# megy_dole_v1.net
KiCad netlist of a schematic drawn in EAGLE
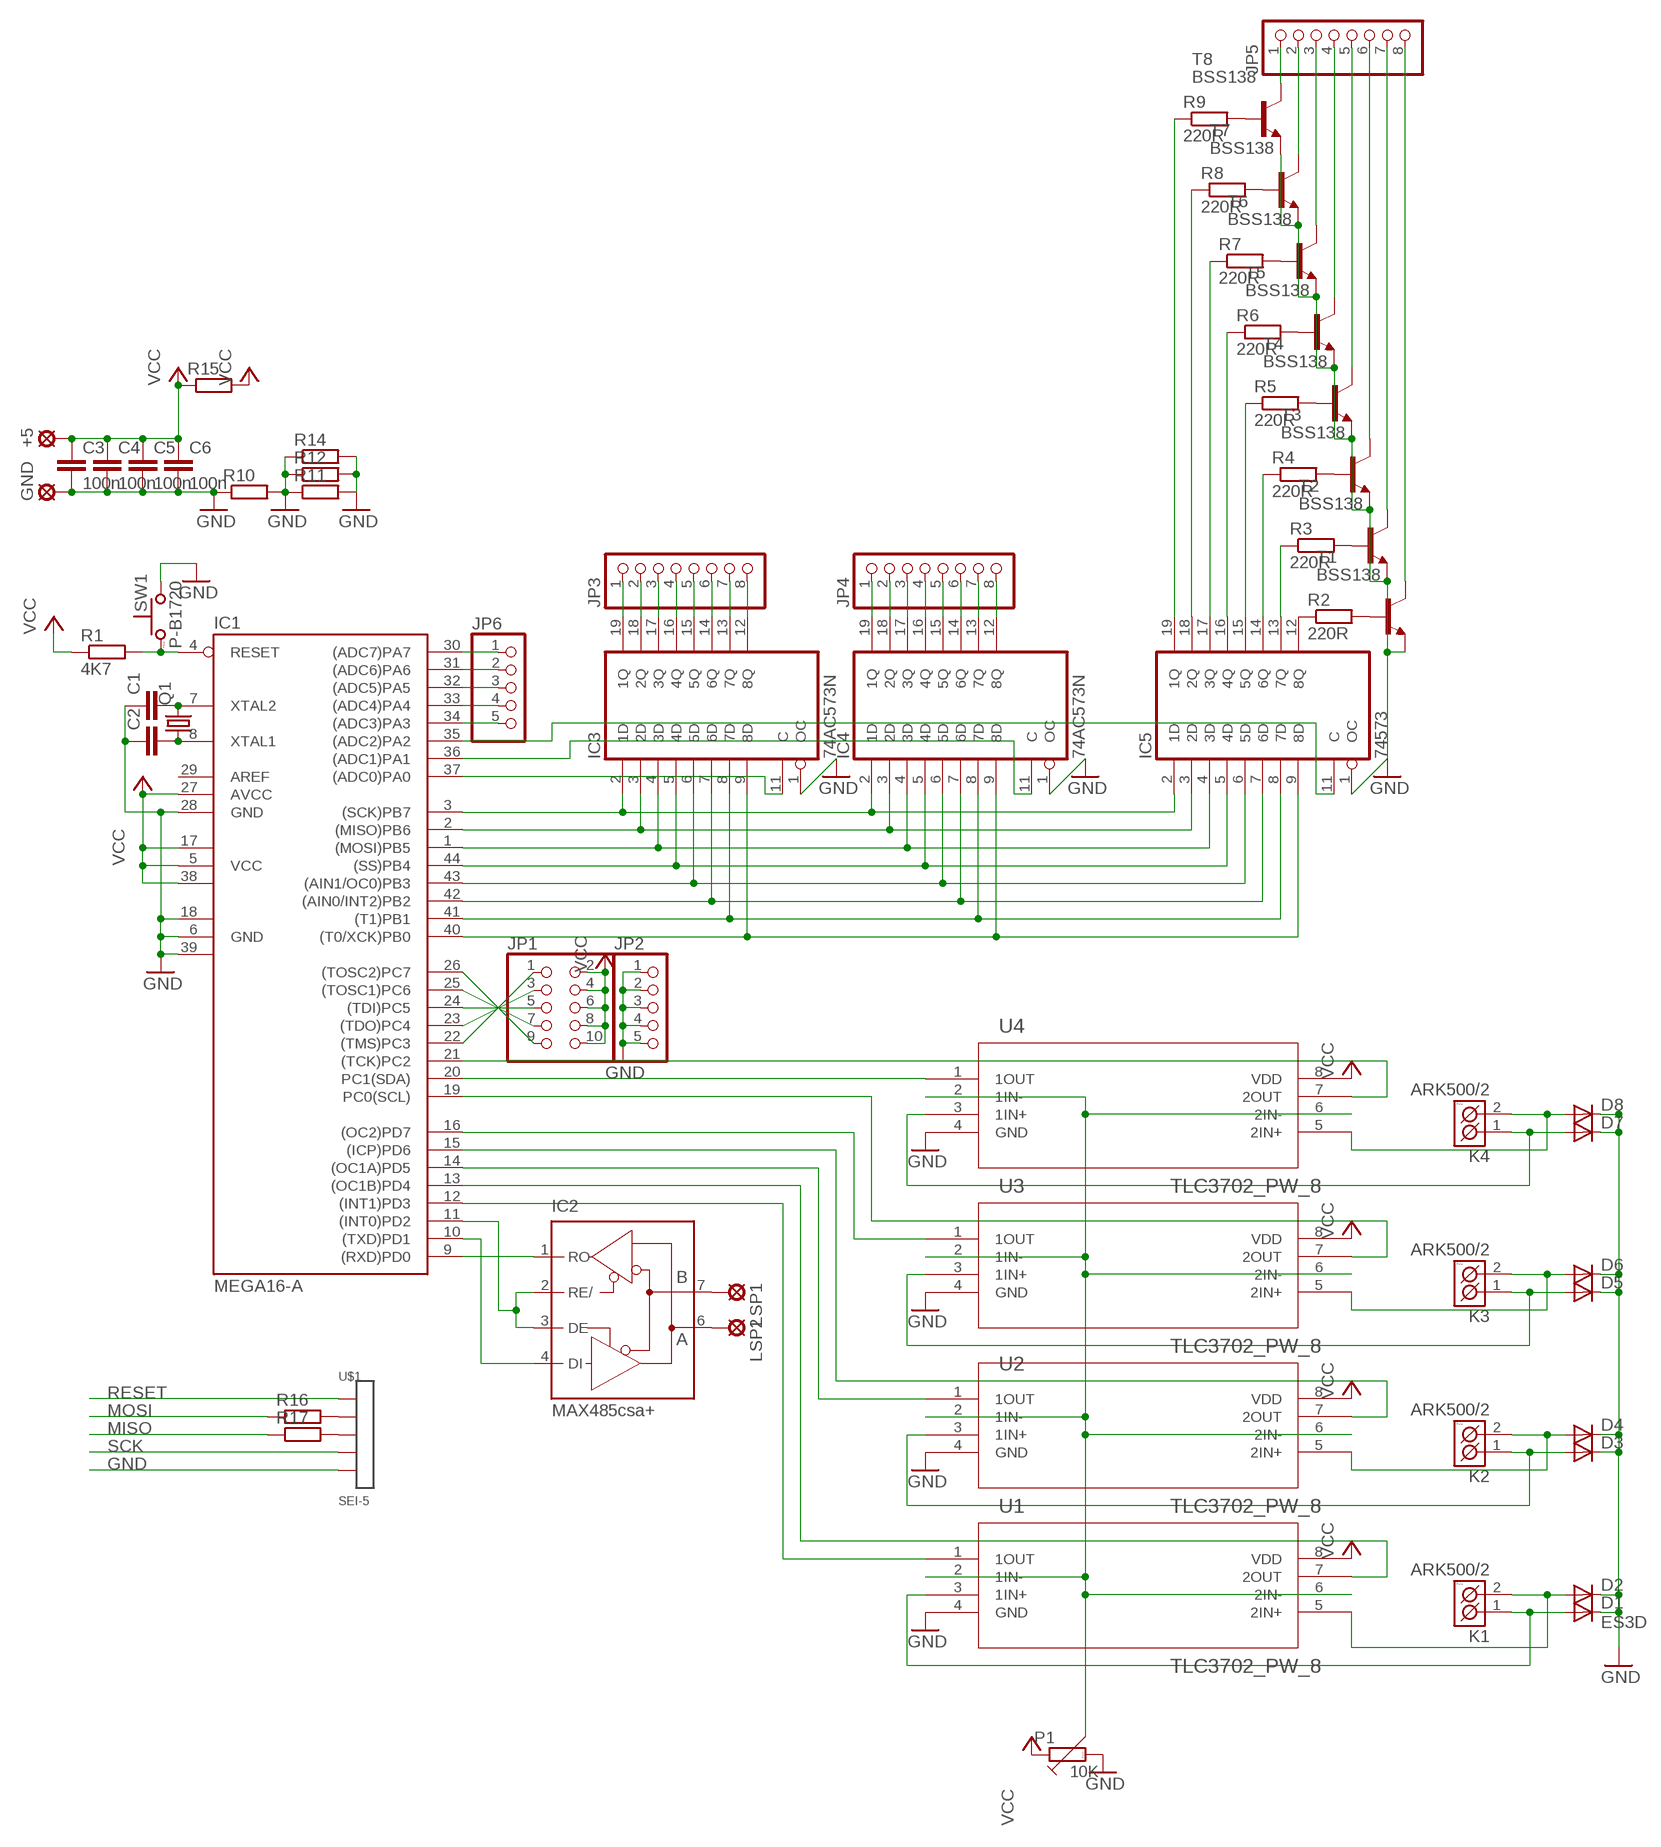
[diagram p0: schematic, sheet 1]

(export (version "E")
  (design (tool "Eeschema 10.0.6"))
  (components
    (comp (ref "+5")
      (value "LSP10")
      (footprint "eagle-import:LSP10")
      (libsource (lib "eagle-import") (part "LSP10"))
    )
    (comp (ref "C1")
      (value "C-EUC0603")
      (footprint "eagle-import:C0603")
      (libsource (lib "eagle-import") (part "C-EUC0603"))
    )
    (comp (ref "C2")
      (value "C-EUC0603")
      (footprint "eagle-import:C0603")
      (libsource (lib "eagle-import") (part "C-EUC0603"))
    )
    (comp (ref "C3")
      (value "100n")
      (footprint "eagle-import:C0504")
      (libsource (lib "eagle-import") (part "C-EUC0504"))
    )
    (comp (ref "C4")
      (value "100n")
      (footprint "eagle-import:C0504")
      (libsource (lib "eagle-import") (part "C-EUC0504"))
    )
    (comp (ref "C5")
      (value "100n")
      (footprint "eagle-import:C0504")
      (libsource (lib "eagle-import") (part "C-EUC0504"))
    )
    (comp (ref "C6")
      (value "100n")
      (footprint "eagle-import:C0504")
      (libsource (lib "eagle-import") (part "C-EUC0504"))
    )
    (comp (ref "D1")
      (value "ES3D")
      (footprint "eagle-import:SMC")
      (libsource (lib "eagle-import") (part "DIODE-SMC"))
    )
    (comp (ref "D2")
      (value "DIODE-SMC")
      (footprint "eagle-import:SMC")
      (libsource (lib "eagle-import") (part "DIODE-SMC"))
    )
    (comp (ref "D3")
      (value "DIODE-SMC")
      (footprint "eagle-import:SMC")
      (libsource (lib "eagle-import") (part "DIODE-SMC"))
    )
    (comp (ref "D4")
      (value "DIODE-SMC")
      (footprint "eagle-import:SMC")
      (libsource (lib "eagle-import") (part "DIODE-SMC"))
    )
    (comp (ref "D5")
      (value "DIODE-SMC")
      (footprint "eagle-import:SMC")
      (libsource (lib "eagle-import") (part "DIODE-SMC"))
    )
    (comp (ref "D6")
      (value "DIODE-SMC")
      (footprint "eagle-import:SMC")
      (libsource (lib "eagle-import") (part "DIODE-SMC"))
    )
    (comp (ref "D7")
      (value "DIODE-SMC")
      (footprint "eagle-import:SMC")
      (libsource (lib "eagle-import") (part "DIODE-SMC"))
    )
    (comp (ref "D8")
      (value "DIODE-SMC")
      (footprint "eagle-import:SMC")
      (libsource (lib "eagle-import") (part "DIODE-SMC"))
    )
    (comp (ref "GND")
      (value "LSP10")
      (footprint "eagle-import:LSP10")
      (libsource (lib "eagle-import") (part "LSP10"))
    )
    (comp (ref "IC1")
      (value "MEGA16-A")
      (footprint "eagle-import:TQFP44")
      (fields (field (name "MPN") "ATMEGA16-16AU"))
      (libsource (lib "eagle-import") (part "MEGA16-A"))
    )
    (comp (ref "IC2")
      (value "MAX485csa+")
      (footprint "eagle-import:SO08")
      (fields
        (field (name "MF") "MAXIM")
        (field (name "MPN") "MAX481CSA")
        (field (name "MF_1") "MAXIM")
        (field (name "MPN_1") "MAX481CSA")
        (field (name "OC_NEWARK") "90C3817")
      )
      (libsource (lib "eagle-import") (part "MAX481CSA"))
    )
    (comp (ref "IC3")
      (value "74AC573N")
      (footprint "eagle-import:DIL20")
      (libsource (lib "eagle-import") (part "74573NAC"))
    )
    (comp (ref "IC4")
      (value "74AC573N")
      (footprint "eagle-import:DIL20")
      (libsource (lib "eagle-import") (part "74573NAC"))
    )
    (comp (ref "IC5")
      (value "74573")
      (footprint "eagle-import:PW20")
      (libsource (lib "eagle-import") (part "74573"))
    )
    (comp (ref "JP1")
      (value "PINHD-2X5")
      (footprint "eagle-import:2X05")
      (libsource (lib "eagle-import") (part "PINHD-2X5"))
    )
    (comp (ref "JP2")
      (value "PINHD-1X5")
      (footprint "eagle-import:1X05")
      (libsource (lib "eagle-import") (part "PINHD-1X5"))
    )
    (comp (ref "JP3")
      (value "PINHD-1X8")
      (footprint "eagle-import:1X08")
      (libsource (lib "eagle-import") (part "PINHD-1X8"))
    )
    (comp (ref "JP4")
      (value "PINHD-1X8")
      (footprint "eagle-import:1X08")
      (libsource (lib "eagle-import") (part "PINHD-1X8"))
    )
    (comp (ref "JP5")
      (value "PINHD-1X8")
      (footprint "eagle-import:1X08")
      (libsource (lib "eagle-import") (part "PINHD-1X8"))
    )
    (comp (ref "JP6")
      (value "PINHD-1X5")
      (footprint "eagle-import:1X05")
      (libsource (lib "eagle-import") (part "PINHD-1X5"))
    )
    (comp (ref "K1")
      (value "ARK500/2")
      (footprint "eagle-import:ARK500_2")
      (libsource (lib "eagle-import") (part "ARK500/2"))
    )
    (comp (ref "K2")
      (value "ARK500/2")
      (footprint "eagle-import:ARK500_2")
      (libsource (lib "eagle-import") (part "ARK500/2"))
    )
    (comp (ref "K3")
      (value "ARK500/2")
      (footprint "eagle-import:ARK500_2")
      (libsource (lib "eagle-import") (part "ARK500/2"))
    )
    (comp (ref "K4")
      (value "ARK500/2")
      (footprint "eagle-import:ARK500_2")
      (libsource (lib "eagle-import") (part "ARK500/2"))
    )
    (comp (ref "LSP1")
      (value "LSP10")
      (footprint "eagle-import:LSP10")
      (libsource (lib "eagle-import") (part "LSP10"))
    )
    (comp (ref "LSP2")
      (value "LSP10")
      (footprint "eagle-import:LSP10")
      (libsource (lib "eagle-import") (part "LSP10"))
    )
    (comp (ref "P1")
      (value "10K")
      (footprint "eagle-import:PM19")
      (libsource (lib "eagle-import") (part "TRIMRPM19"))
    )
    (comp (ref "Q1")
      (value "CRYSTALHC49UP")
      (footprint "eagle-import:HC49UP")
      (libsource (lib "eagle-import") (part "CRYSTALHC49UP"))
    )
    (comp (ref "R1")
      (value "4K7")
      (footprint "eagle-import:R0402")
      (libsource (lib "eagle-import") (part "R-EU_R0402"))
    )
    (comp (ref "R2")
      (value "220R")
      (footprint "eagle-import:R0402")
      (libsource (lib "eagle-import") (part "R-EU_R0402"))
    )
    (comp (ref "R3")
      (value "220R")
      (footprint "eagle-import:R0402")
      (libsource (lib "eagle-import") (part "R-EU_R0402"))
    )
    (comp (ref "R4")
      (value "220R")
      (footprint "eagle-import:R0402")
      (libsource (lib "eagle-import") (part "R-EU_R0402"))
    )
    (comp (ref "R5")
      (value "220R")
      (footprint "eagle-import:R0402")
      (libsource (lib "eagle-import") (part "R-EU_R0402"))
    )
    (comp (ref "R6")
      (value "220R")
      (footprint "eagle-import:R0402")
      (libsource (lib "eagle-import") (part "R-EU_R0402"))
    )
    (comp (ref "R7")
      (value "220R")
      (footprint "eagle-import:R0402")
      (libsource (lib "eagle-import") (part "R-EU_R0402"))
    )
    (comp (ref "R8")
      (value "220R")
      (footprint "eagle-import:R0402")
      (libsource (lib "eagle-import") (part "R-EU_R0402"))
    )
    (comp (ref "R9")
      (value "220R")
      (footprint "eagle-import:R0402")
      (libsource (lib "eagle-import") (part "R-EU_R0402"))
    )
    (comp (ref "R10")
      (value "R-EU_R1206")
      (footprint "eagle-import:R1206")
      (libsource (lib "eagle-import") (part "R-EU_R1206"))
    )
    (comp (ref "R11")
      (value "R-EU_R1206")
      (footprint "eagle-import:R1206")
      (libsource (lib "eagle-import") (part "R-EU_R1206"))
    )
    (comp (ref "R12")
      (value "R-EU_R1206")
      (footprint "eagle-import:R1206")
      (libsource (lib "eagle-import") (part "R-EU_R1206"))
    )
    (comp (ref "R14")
      (value "R-EU_R1206")
      (footprint "eagle-import:R1206")
      (libsource (lib "eagle-import") (part "R-EU_R1206"))
    )
    (comp (ref "R15")
      (value "R-EU_R1206")
      (footprint "eagle-import:R1206")
      (libsource (lib "eagle-import") (part "R-EU_R1206"))
    )
    (comp (ref "R16")
      (value "R-EU_R1206")
      (footprint "eagle-import:R1206")
      (libsource (lib "eagle-import") (part "R-EU_R1206"))
    )
    (comp (ref "R17")
      (value "R-EU_R1206")
      (footprint "eagle-import:R1206")
      (libsource (lib "eagle-import") (part "R-EU_R1206"))
    )
    (comp (ref "SW1")
      (value "P-B1720")
      (footprint "eagle-import:P-B1720")
      (libsource (lib "eagle-import") (part "P-B1720"))
    )
    (comp (ref "T1")
      (value "BSS138")
      (footprint "eagle-import:SOT23")
      (libsource (lib "eagle-import") (part "BC846"))
    )
    (comp (ref "T2")
      (value "BSS138")
      (footprint "eagle-import:SOT23")
      (libsource (lib "eagle-import") (part "BC846"))
    )
    (comp (ref "T3")
      (value "BSS138")
      (footprint "eagle-import:SOT23")
      (libsource (lib "eagle-import") (part "BC846"))
    )
    (comp (ref "T4")
      (value "BSS138")
      (footprint "eagle-import:SOT23")
      (libsource (lib "eagle-import") (part "BC846"))
    )
    (comp (ref "T5")
      (value "BSS138")
      (footprint "eagle-import:SOT23")
      (libsource (lib "eagle-import") (part "BC846"))
    )
    (comp (ref "T6")
      (value "BSS138")
      (footprint "eagle-import:SOT23")
      (libsource (lib "eagle-import") (part "BC846"))
    )
    (comp (ref "T7")
      (value "BSS138")
      (footprint "eagle-import:SOT23")
      (libsource (lib "eagle-import") (part "BC846"))
    )
    (comp (ref "T8")
      (value "BSS138")
      (footprint "eagle-import:SOT23")
      (libsource (lib "eagle-import") (part "BC846"))
    )
    (comp (ref "U$1")
      (value "SEI-5")
      (footprint "eagle-import:SEI-5")
      (libsource (lib "eagle-import") (part "SEI-5"))
    )
    (comp (ref "U1")
      (value "TLC3702_PW_8")
      (footprint "eagle-import:PW8")
      (fields
        (field (name "GENERIC_PART_NUMBER") "TLC3702")
        (field (name "MANUFACTURER") "Texas Instruments")
        (field (name "MANUFACTURER_PART_NUMBER") "tlc3702_pw_8")
      )
      (libsource (lib "eagle-import") (part "TLC3702_PW_8"))
    )
    (comp (ref "U2")
      (value "TLC3702_PW_8")
      (footprint "eagle-import:PW8")
      (fields
        (field (name "GENERIC_PART_NUMBER") "TLC3702")
        (field (name "MANUFACTURER") "Texas Instruments")
        (field (name "MANUFACTURER_PART_NUMBER") "tlc3702_pw_8")
      )
      (libsource (lib "eagle-import") (part "TLC3702_PW_8"))
    )
    (comp (ref "U3")
      (value "TLC3702_PW_8")
      (footprint "eagle-import:PW8")
      (fields
        (field (name "GENERIC_PART_NUMBER") "TLC3702")
        (field (name "MANUFACTURER") "Texas Instruments")
        (field (name "MANUFACTURER_PART_NUMBER") "tlc3702_pw_8")
      )
      (libsource (lib "eagle-import") (part "TLC3702_PW_8"))
    )
    (comp (ref "U4")
      (value "TLC3702_PW_8")
      (footprint "eagle-import:PW8")
      (fields
        (field (name "GENERIC_PART_NUMBER") "TLC3702")
        (field (name "MANUFACTURER") "Texas Instruments")
        (field (name "MANUFACTURER_PART_NUMBER") "tlc3702_pw_8")
      )
      (libsource (lib "eagle-import") (part "TLC3702_PW_8"))
    )
  )
  (nets
    (net (code "1") (name "/MISO") (class "Default")
      (node (ref "IC1") (pin "2") (pinfunction "(MISO)PB6_2") (pintype "bidirectional"))
      (node (ref "IC3") (pin "3") (pinfunction "2D_3") (pintype "input"))
      (node (ref "IC4") (pin "3") (pinfunction "2D_3") (pintype "input"))
      (node (ref "IC5") (pin "3") (pinfunction "2D_3") (pintype "input"))
      (node (ref "R17") (pin "1") (pinfunction "1_1") (pintype "passive"))
    )
    (net (code "2") (name "/MOSI") (class "Default")
      (node (ref "IC1") (pin "1") (pinfunction "(MOSI)PB5_1") (pintype "bidirectional"))
      (node (ref "IC3") (pin "4") (pinfunction "3D_4") (pintype "input"))
      (node (ref "IC4") (pin "4") (pinfunction "3D_4") (pintype "input"))
      (node (ref "IC5") (pin "4") (pinfunction "3D_4") (pintype "input"))
      (node (ref "R16") (pin "1") (pinfunction "1_1") (pintype "passive"))
    )
    (net (code "3") (name "/RESET") (class "Default")
      (node (ref "IC1") (pin "4") (pinfunction "RESET_4") (pintype "input"))
      (node (ref "R1") (pin "2") (pinfunction "2_2") (pintype "passive"))
      (node (ref "SW1") (pin "1") (pinfunction "1_1") (pintype "passive"))
      (node (ref "U$1") (pin "P$1") (pinfunction "P$1_P$1") (pintype "bidirectional"))
    )
    (net (code "4") (name "/SCK") (class "Default")
      (node (ref "IC1") (pin "3") (pinfunction "(SCK)PB7_3") (pintype "bidirectional"))
      (node (ref "IC3") (pin "2") (pinfunction "1D_2") (pintype "input"))
      (node (ref "IC4") (pin "2") (pinfunction "1D_2") (pintype "input"))
      (node (ref "IC5") (pin "2") (pinfunction "1D_2") (pintype "input"))
      (node (ref "U$1") (pin "P$4") (pinfunction "P$4_P$4") (pintype "bidirectional"))
    )
    (net (code "5") (name "GND") (class "Default")
      (node (ref "C1") (pin "1") (pinfunction "1_1") (pintype "passive"))
      (node (ref "C2") (pin "1") (pinfunction "1_1") (pintype "passive"))
      (node (ref "C3") (pin "2") (pinfunction "2_2") (pintype "passive"))
      (node (ref "C4") (pin "2") (pinfunction "2_2") (pintype "passive"))
      (node (ref "C5") (pin "2") (pinfunction "2_2") (pintype "passive"))
      (node (ref "C6") (pin "2") (pinfunction "2_2") (pintype "passive"))
      (node (ref "D1") (pin "C") (pinfunction "C_C") (pintype "passive"))
      (node (ref "D2") (pin "C") (pinfunction "C_C") (pintype "passive"))
      (node (ref "D3") (pin "C") (pinfunction "C_C") (pintype "passive"))
      (node (ref "D4") (pin "C") (pinfunction "C_C") (pintype "passive"))
      (node (ref "D5") (pin "C") (pinfunction "C_C") (pintype "passive"))
      (node (ref "D6") (pin "C") (pinfunction "C_C") (pintype "passive"))
      (node (ref "D7") (pin "C") (pinfunction "C_C") (pintype "passive"))
      (node (ref "D8") (pin "C") (pinfunction "C_C") (pintype "passive"))
      (node (ref "GND") (pin "MP") (pinfunction "MP_MP") (pintype "passive"))
      (node (ref "IC1") (pin "18") (pinfunction "GND1_18") (pintype "power_in"))
      (node (ref "IC1") (pin "28") (pinfunction "GND_28") (pintype "power_in"))
      (node (ref "IC1") (pin "39") (pinfunction "GND2_39") (pintype "power_in"))
      (node (ref "IC1") (pin "6") (pinfunction "GND_6") (pintype "power_in"))
      (node (ref "IC3") (pin "1") (pinfunction "OC_1") (pintype "input"))
      (node (ref "IC4") (pin "1") (pinfunction "OC_1") (pintype "input"))
      (node (ref "IC5") (pin "1") (pinfunction "OC_1") (pintype "input"))
      (node (ref "JP2") (pin "1") (pinfunction "1_1") (pintype "passive"))
      (node (ref "JP2") (pin "2") (pinfunction "2_2") (pintype "passive"))
      (node (ref "JP2") (pin "3") (pinfunction "3_3") (pintype "passive"))
      (node (ref "JP2") (pin "4") (pinfunction "4_4") (pintype "passive"))
      (node (ref "JP2") (pin "5") (pinfunction "5_5") (pintype "passive"))
      (node (ref "P1") (pin "B") (pinfunction "2_B") (pintype "passive"))
      (node (ref "R10") (pin "1") (pinfunction "1_1") (pintype "passive"))
      (node (ref "R10") (pin "2") (pinfunction "2_2") (pintype "passive"))
      (node (ref "R11") (pin "1") (pinfunction "1_1") (pintype "passive"))
      (node (ref "R11") (pin "2") (pinfunction "2_2") (pintype "passive"))
      (node (ref "R12") (pin "1") (pinfunction "1_1") (pintype "passive"))
      (node (ref "R12") (pin "2") (pinfunction "2_2") (pintype "passive"))
      (node (ref "R14") (pin "1") (pinfunction "1_1") (pintype "passive"))
      (node (ref "R14") (pin "2") (pinfunction "2_2") (pintype "passive"))
      (node (ref "SW1") (pin "2") (pinfunction "2_2") (pintype "passive"))
      (node (ref "T1") (pin "2") (pinfunction "E_2") (pintype "passive"))
      (node (ref "T2") (pin "2") (pinfunction "E_2") (pintype "passive"))
      (node (ref "T3") (pin "2") (pinfunction "E_2") (pintype "passive"))
      (node (ref "T4") (pin "2") (pinfunction "E_2") (pintype "passive"))
      (node (ref "T5") (pin "2") (pinfunction "E_2") (pintype "passive"))
      (node (ref "T6") (pin "2") (pinfunction "E_2") (pintype "passive"))
      (node (ref "T7") (pin "2") (pinfunction "E_2") (pintype "passive"))
      (node (ref "T8") (pin "2") (pinfunction "E_2") (pintype "passive"))
      (node (ref "U$1") (pin "P$5") (pinfunction "P$5_P$5") (pintype "bidirectional"))
      (node (ref "U1") (pin "4") (pinfunction "GND_4") (pintype "power_in"))
      (node (ref "U2") (pin "4") (pinfunction "GND_4") (pintype "power_in"))
      (node (ref "U3") (pin "4") (pinfunction "GND_4") (pintype "power_in"))
      (node (ref "U4") (pin "4") (pinfunction "GND_4") (pintype "power_in"))
    )
    (net (code "6") (name "Net-(IC1-(ADC0)PA0)") (class "Default")
      (node (ref "IC1") (pin "37") (pinfunction "(ADC0)PA0_37") (pintype "bidirectional"))
      (node (ref "IC3") (pin "11") (pinfunction "C_11") (pintype "input"))
    )
    (net (code "7") (name "Net-(IC1-(ADC1)PA1)") (class "Default")
      (node (ref "IC1") (pin "36") (pinfunction "(ADC1)PA1_36") (pintype "bidirectional"))
      (node (ref "IC4") (pin "11") (pinfunction "C_11") (pintype "input"))
    )
    (net (code "8") (name "Net-(IC1-(ADC2)PA2)") (class "Default")
      (node (ref "IC1") (pin "35") (pinfunction "(ADC2)PA2_35") (pintype "bidirectional"))
      (node (ref "IC5") (pin "11") (pinfunction "C_11") (pintype "input"))
    )
    (net (code "9") (name "Net-(IC1-(ADC3)PA3)") (class "Default")
      (node (ref "IC1") (pin "34") (pinfunction "(ADC3)PA3_34") (pintype "bidirectional"))
      (node (ref "JP6") (pin "5") (pinfunction "5_5") (pintype "passive"))
    )
    (net (code "10") (name "Net-(IC1-(ADC4)PA4)") (class "Default")
      (node (ref "IC1") (pin "33") (pinfunction "(ADC4)PA4_33") (pintype "bidirectional"))
      (node (ref "JP6") (pin "4") (pinfunction "4_4") (pintype "passive"))
    )
    (net (code "11") (name "Net-(IC1-(ADC5)PA5)") (class "Default")
      (node (ref "IC1") (pin "32") (pinfunction "(ADC5)PA5_32") (pintype "bidirectional"))
      (node (ref "JP6") (pin "3") (pinfunction "3_3") (pintype "passive"))
    )
    (net (code "12") (name "Net-(IC1-(ADC6)PA6)") (class "Default")
      (node (ref "IC1") (pin "31") (pinfunction "(ADC6)PA6_31") (pintype "bidirectional"))
      (node (ref "JP6") (pin "2") (pinfunction "2_2") (pintype "passive"))
    )
    (net (code "13") (name "Net-(IC1-(ADC7)PA7)") (class "Default")
      (node (ref "IC1") (pin "30") (pinfunction "(ADC7)PA7_30") (pintype "bidirectional"))
      (node (ref "JP6") (pin "1") (pinfunction "1_1") (pintype "passive"))
    )
    (net (code "14") (name "Net-(IC1-(AIN0{slash}INT2)PB2)") (class "Default")
      (node (ref "IC1") (pin "42") (pinfunction "(AIN0/INT2)PB2_42") (pintype "bidirectional"))
      (node (ref "IC3") (pin "7") (pinfunction "6D_7") (pintype "input"))
      (node (ref "IC4") (pin "7") (pinfunction "6D_7") (pintype "input"))
      (node (ref "IC5") (pin "7") (pinfunction "6D_7") (pintype "input"))
    )
    (net (code "15") (name "Net-(IC1-(AIN1{slash}OC0)PB3)") (class "Default")
      (node (ref "IC1") (pin "43") (pinfunction "(AIN1/OC0)PB3_43") (pintype "bidirectional"))
      (node (ref "IC3") (pin "6") (pinfunction "5D_6") (pintype "input"))
      (node (ref "IC4") (pin "6") (pinfunction "5D_6") (pintype "input"))
      (node (ref "IC5") (pin "6") (pinfunction "5D_6") (pintype "input"))
    )
    (net (code "16") (name "Net-(IC1-(ICP)PD6)") (class "Default")
      (node (ref "IC1") (pin "15") (pinfunction "(ICP)PD6_15") (pintype "bidirectional"))
      (node (ref "U2") (pin "7") (pinfunction "2OUT_7") (pintype "output"))
    )
    (net (code "17") (name "Net-(IC1-(INT0)PD2)") (class "Default")
      (node (ref "IC1") (pin "11") (pinfunction "(INT0)PD2_11") (pintype "bidirectional"))
      (node (ref "IC2") (pin "2") (pinfunction "RE/_2") (pintype "input"))
      (node (ref "IC2") (pin "3") (pinfunction "DE_3") (pintype "input"))
    )
    (net (code "18") (name "Net-(IC1-(INT1)PD3)") (class "Default")
      (node (ref "IC1") (pin "12") (pinfunction "(INT1)PD3_12") (pintype "bidirectional"))
      (node (ref "U1") (pin "1") (pinfunction "1OUT_1") (pintype "output"))
    )
    (net (code "19") (name "Net-(IC1-(OC1A)PD5)") (class "Default")
      (node (ref "IC1") (pin "14") (pinfunction "(OC1A)PD5_14") (pintype "bidirectional"))
      (node (ref "U2") (pin "1") (pinfunction "1OUT_1") (pintype "output"))
    )
    (net (code "20") (name "Net-(IC1-(OC1B)PD4)") (class "Default")
      (node (ref "IC1") (pin "13") (pinfunction "(OC1B)PD4_13") (pintype "bidirectional"))
      (node (ref "U1") (pin "7") (pinfunction "2OUT_7") (pintype "output"))
    )
    (net (code "21") (name "Net-(IC1-(OC2)PD7)") (class "Default")
      (node (ref "IC1") (pin "16") (pinfunction "(OC2)PD7_16") (pintype "bidirectional"))
      (node (ref "U3") (pin "1") (pinfunction "1OUT_1") (pintype "output"))
    )
    (net (code "22") (name "Net-(IC1-(RXD)PD0)") (class "Default")
      (node (ref "IC1") (pin "9") (pinfunction "(RXD)PD0_9") (pintype "bidirectional"))
      (node (ref "IC2") (pin "1") (pinfunction "RO_1") (pintype "output"))
    )
    (net (code "23") (name "Net-(IC1-(SS)PB4)") (class "Default")
      (node (ref "IC1") (pin "44") (pinfunction "(SS)PB4_44") (pintype "bidirectional"))
      (node (ref "IC3") (pin "5") (pinfunction "4D_5") (pintype "input"))
      (node (ref "IC4") (pin "5") (pinfunction "4D_5") (pintype "input"))
      (node (ref "IC5") (pin "5") (pinfunction "4D_5") (pintype "input"))
    )
    (net (code "24") (name "Net-(IC1-(T0{slash}XCK)PB0)") (class "Default")
      (node (ref "IC1") (pin "40") (pinfunction "(T0/XCK)PB0_40") (pintype "bidirectional"))
      (node (ref "IC3") (pin "9") (pinfunction "8D_9") (pintype "input"))
      (node (ref "IC4") (pin "9") (pinfunction "8D_9") (pintype "input"))
      (node (ref "IC5") (pin "9") (pinfunction "8D_9") (pintype "input"))
    )
    (net (code "25") (name "Net-(IC1-(T1)PB1)") (class "Default")
      (node (ref "IC1") (pin "41") (pinfunction "(T1)PB1_41") (pintype "bidirectional"))
      (node (ref "IC3") (pin "8") (pinfunction "7D_8") (pintype "input"))
      (node (ref "IC4") (pin "8") (pinfunction "7D_8") (pintype "input"))
      (node (ref "IC5") (pin "8") (pinfunction "7D_8") (pintype "input"))
    )
    (net (code "26") (name "Net-(IC1-(TCK)PC2)") (class "Default")
      (node (ref "IC1") (pin "21") (pinfunction "(TCK)PC2_21") (pintype "bidirectional"))
      (node (ref "U4") (pin "7") (pinfunction "2OUT_7") (pintype "output"))
    )
    (net (code "27") (name "Net-(IC1-(TDI)PC5)") (class "Default")
      (node (ref "IC1") (pin "24") (pinfunction "(TDI)PC5_24") (pintype "bidirectional"))
      (node (ref "JP1") (pin "5") (pinfunction "5_5") (pintype "passive"))
    )
    (net (code "28") (name "Net-(IC1-(TDO)PC4)") (class "Default")
      (node (ref "IC1") (pin "23") (pinfunction "(TDO)PC4_23") (pintype "bidirectional"))
      (node (ref "JP1") (pin "3") (pinfunction "3_3") (pintype "passive"))
    )
    (net (code "29") (name "Net-(IC1-(TMS)PC3)") (class "Default")
      (node (ref "IC1") (pin "22") (pinfunction "(TMS)PC3_22") (pintype "bidirectional"))
      (node (ref "JP1") (pin "1") (pinfunction "1_1") (pintype "passive"))
    )
    (net (code "30") (name "Net-(IC1-(TOSC1)PC6)") (class "Default")
      (node (ref "IC1") (pin "25") (pinfunction "(TOSC1)PC6_25") (pintype "bidirectional"))
      (node (ref "JP1") (pin "7") (pinfunction "7_7") (pintype "passive"))
    )
    (net (code "31") (name "Net-(IC1-(TOSC2)PC7)") (class "Default")
      (node (ref "IC1") (pin "26") (pinfunction "(TOSC2)PC7_26") (pintype "bidirectional"))
      (node (ref "JP1") (pin "9") (pinfunction "9_9") (pintype "passive"))
    )
    (net (code "32") (name "Net-(IC1-(TXD)PD1)") (class "Default")
      (node (ref "IC1") (pin "10") (pinfunction "(TXD)PD1_10") (pintype "bidirectional"))
      (node (ref "IC2") (pin "4") (pinfunction "DI_4") (pintype "input"))
    )
    (net (code "33") (name "Net-(IC1-PC0(SCL))") (class "Default")
      (node (ref "IC1") (pin "19") (pinfunction "PC0(SCL)_19") (pintype "bidirectional"))
      (node (ref "U3") (pin "7") (pinfunction "2OUT_7") (pintype "output"))
    )
    (net (code "34") (name "Net-(IC1-PC1(SDA))") (class "Default")
      (node (ref "IC1") (pin "20") (pinfunction "PC1(SDA)_20") (pintype "bidirectional"))
      (node (ref "U4") (pin "1") (pinfunction "1OUT_1") (pintype "output"))
    )
    (net (code "35") (name "Net-(IC1-XTAL1)") (class "Default")
      (node (ref "C2") (pin "2") (pinfunction "2_2") (pintype "passive"))
      (node (ref "IC1") (pin "8") (pinfunction "XTAL1_8") (pintype "bidirectional"))
      (node (ref "Q1") (pin "1") (pinfunction "1_1") (pintype "passive"))
    )
    (net (code "36") (name "Net-(IC1-XTAL2)") (class "Default")
      (node (ref "C1") (pin "2") (pinfunction "2_2") (pintype "passive"))
      (node (ref "IC1") (pin "7") (pinfunction "XTAL2_7") (pintype "bidirectional"))
      (node (ref "Q1") (pin "2") (pinfunction "2_2") (pintype "passive"))
    )
    (net (code "37") (name "Net-(IC2A-A)") (class "Default")
      (node (ref "IC2") (pin "6") (pinfunction "A_6") (pintype "passive"))
      (node (ref "LSP2") (pin "MP") (pinfunction "MP_MP") (pintype "passive"))
    )
    (net (code "38") (name "Net-(IC2A-B)") (class "Default")
      (node (ref "IC2") (pin "7") (pinfunction "B_7") (pintype "passive"))
      (node (ref "LSP1") (pin "MP") (pinfunction "MP_MP") (pintype "passive"))
    )
    (net (code "39") (name "Net-(IC3A-1Q)") (class "Default")
      (node (ref "IC3") (pin "19") (pinfunction "1Q_19") (pintype "tri_state"))
      (node (ref "JP3") (pin "1") (pinfunction "1_1") (pintype "passive"))
    )
    (net (code "40") (name "Net-(IC3A-2Q)") (class "Default")
      (node (ref "IC3") (pin "18") (pinfunction "2Q_18") (pintype "tri_state"))
      (node (ref "JP3") (pin "2") (pinfunction "2_2") (pintype "passive"))
    )
    (net (code "41") (name "Net-(IC3A-3Q)") (class "Default")
      (node (ref "IC3") (pin "17") (pinfunction "3Q_17") (pintype "tri_state"))
      (node (ref "JP3") (pin "3") (pinfunction "3_3") (pintype "passive"))
    )
    (net (code "42") (name "Net-(IC3A-4Q)") (class "Default")
      (node (ref "IC3") (pin "16") (pinfunction "4Q_16") (pintype "tri_state"))
      (node (ref "JP3") (pin "4") (pinfunction "4_4") (pintype "passive"))
    )
    (net (code "43") (name "Net-(IC3A-5Q)") (class "Default")
      (node (ref "IC3") (pin "15") (pinfunction "5Q_15") (pintype "tri_state"))
      (node (ref "JP3") (pin "5") (pinfunction "5_5") (pintype "passive"))
    )
    (net (code "44") (name "Net-(IC3A-6Q)") (class "Default")
      (node (ref "IC3") (pin "14") (pinfunction "6Q_14") (pintype "tri_state"))
      (node (ref "JP3") (pin "6") (pinfunction "6_6") (pintype "passive"))
    )
    (net (code "45") (name "Net-(IC3A-7Q)") (class "Default")
      (node (ref "IC3") (pin "13") (pinfunction "7Q_13") (pintype "tri_state"))
      (node (ref "JP3") (pin "7") (pinfunction "7_7") (pintype "passive"))
    )
    (net (code "46") (name "Net-(IC3A-8Q)") (class "Default")
      (node (ref "IC3") (pin "12") (pinfunction "8Q_12") (pintype "tri_state"))
      (node (ref "JP3") (pin "8") (pinfunction "8_8") (pintype "passive"))
    )
    (net (code "47") (name "Net-(IC4A-1Q)") (class "Default")
      (node (ref "IC4") (pin "19") (pinfunction "1Q_19") (pintype "tri_state"))
      (node (ref "JP4") (pin "1") (pinfunction "1_1") (pintype "passive"))
    )
    (net (code "48") (name "Net-(IC4A-2Q)") (class "Default")
      (node (ref "IC4") (pin "18") (pinfunction "2Q_18") (pintype "tri_state"))
      (node (ref "JP4") (pin "2") (pinfunction "2_2") (pintype "passive"))
    )
    (net (code "49") (name "Net-(IC4A-3Q)") (class "Default")
      (node (ref "IC4") (pin "17") (pinfunction "3Q_17") (pintype "tri_state"))
      (node (ref "JP4") (pin "3") (pinfunction "3_3") (pintype "passive"))
    )
    (net (code "50") (name "Net-(IC4A-4Q)") (class "Default")
      (node (ref "IC4") (pin "16") (pinfunction "4Q_16") (pintype "tri_state"))
      (node (ref "JP4") (pin "4") (pinfunction "4_4") (pintype "passive"))
    )
    (net (code "51") (name "Net-(IC4A-5Q)") (class "Default")
      (node (ref "IC4") (pin "15") (pinfunction "5Q_15") (pintype "tri_state"))
      (node (ref "JP4") (pin "5") (pinfunction "5_5") (pintype "passive"))
    )
    (net (code "52") (name "Net-(IC4A-6Q)") (class "Default")
      (node (ref "IC4") (pin "14") (pinfunction "6Q_14") (pintype "tri_state"))
      (node (ref "JP4") (pin "6") (pinfunction "6_6") (pintype "passive"))
    )
    (net (code "53") (name "Net-(IC4A-7Q)") (class "Default")
      (node (ref "IC4") (pin "13") (pinfunction "7Q_13") (pintype "tri_state"))
      (node (ref "JP4") (pin "7") (pinfunction "7_7") (pintype "passive"))
    )
    (net (code "54") (name "Net-(IC4A-8Q)") (class "Default")
      (node (ref "IC4") (pin "12") (pinfunction "8Q_12") (pintype "tri_state"))
      (node (ref "JP4") (pin "8") (pinfunction "8_8") (pintype "passive"))
    )
    (net (code "55") (name "Net-(IC5A-1Q)") (class "Default")
      (node (ref "IC5") (pin "19") (pinfunction "1Q_19") (pintype "tri_state"))
      (node (ref "R9") (pin "1") (pinfunction "1_1") (pintype "passive"))
    )
    (net (code "56") (name "Net-(IC5A-2Q)") (class "Default")
      (node (ref "IC5") (pin "18") (pinfunction "2Q_18") (pintype "tri_state"))
      (node (ref "R8") (pin "1") (pinfunction "1_1") (pintype "passive"))
    )
    (net (code "57") (name "Net-(IC5A-3Q)") (class "Default")
      (node (ref "IC5") (pin "17") (pinfunction "3Q_17") (pintype "tri_state"))
      (node (ref "R7") (pin "1") (pinfunction "1_1") (pintype "passive"))
    )
    (net (code "58") (name "Net-(IC5A-4Q)") (class "Default")
      (node (ref "IC5") (pin "16") (pinfunction "4Q_16") (pintype "tri_state"))
      (node (ref "R6") (pin "1") (pinfunction "1_1") (pintype "passive"))
    )
    (net (code "59") (name "Net-(IC5A-5Q)") (class "Default")
      (node (ref "IC5") (pin "15") (pinfunction "5Q_15") (pintype "tri_state"))
      (node (ref "R5") (pin "1") (pinfunction "1_1") (pintype "passive"))
    )
    (net (code "60") (name "Net-(IC5A-6Q)") (class "Default")
      (node (ref "IC5") (pin "14") (pinfunction "6Q_14") (pintype "tri_state"))
      (node (ref "R4") (pin "1") (pinfunction "1_1") (pintype "passive"))
    )
    (net (code "61") (name "Net-(IC5A-7Q)") (class "Default")
      (node (ref "IC5") (pin "13") (pinfunction "7Q_13") (pintype "tri_state"))
      (node (ref "R3") (pin "1") (pinfunction "1_1") (pintype "passive"))
    )
    (net (code "62") (name "Net-(IC5A-8Q)") (class "Default")
      (node (ref "IC5") (pin "12") (pinfunction "8Q_12") (pintype "tri_state"))
      (node (ref "R2") (pin "1") (pinfunction "1_1") (pintype "passive"))
    )
    (net (code "63") (name "Net-(K1-K1)") (class "Default")
      (node (ref "D1") (pin "A") (pinfunction "A_A") (pintype "passive"))
      (node (ref "K1") (pin "1") (pinfunction "K1_1") (pintype "passive"))
      (node (ref "U1") (pin "3") (pinfunction "1IN+_3") (pintype "input"))
    )
    (net (code "64") (name "Net-(K1-K2)") (class "Default")
      (node (ref "D2") (pin "A") (pinfunction "A_A") (pintype "passive"))
      (node (ref "K1") (pin "2") (pinfunction "K2_2") (pintype "passive"))
      (node (ref "U1") (pin "5") (pinfunction "2IN+_5") (pintype "input"))
    )
    (net (code "65") (name "Net-(K2-K1)") (class "Default")
      (node (ref "D3") (pin "A") (pinfunction "A_A") (pintype "passive"))
      (node (ref "K2") (pin "1") (pinfunction "K1_1") (pintype "passive"))
      (node (ref "U2") (pin "3") (pinfunction "1IN+_3") (pintype "input"))
    )
    (net (code "66") (name "Net-(K2-K2)") (class "Default")
      (node (ref "D4") (pin "A") (pinfunction "A_A") (pintype "passive"))
      (node (ref "K2") (pin "2") (pinfunction "K2_2") (pintype "passive"))
      (node (ref "U2") (pin "5") (pinfunction "2IN+_5") (pintype "input"))
    )
    (net (code "67") (name "Net-(K3-K1)") (class "Default")
      (node (ref "D5") (pin "A") (pinfunction "A_A") (pintype "passive"))
      (node (ref "K3") (pin "1") (pinfunction "K1_1") (pintype "passive"))
      (node (ref "U3") (pin "3") (pinfunction "1IN+_3") (pintype "input"))
    )
    (net (code "68") (name "Net-(K3-K2)") (class "Default")
      (node (ref "D6") (pin "A") (pinfunction "A_A") (pintype "passive"))
      (node (ref "K3") (pin "2") (pinfunction "K2_2") (pintype "passive"))
      (node (ref "U3") (pin "5") (pinfunction "2IN+_5") (pintype "input"))
    )
    (net (code "69") (name "Net-(K4-K1)") (class "Default")
      (node (ref "D7") (pin "A") (pinfunction "A_A") (pintype "passive"))
      (node (ref "K4") (pin "1") (pinfunction "K1_1") (pintype "passive"))
      (node (ref "U4") (pin "3") (pinfunction "1IN+_3") (pintype "input"))
    )
    (net (code "70") (name "Net-(K4-K2)") (class "Default")
      (node (ref "D8") (pin "A") (pinfunction "A_A") (pintype "passive"))
      (node (ref "K4") (pin "2") (pinfunction "K2_2") (pintype "passive"))
      (node (ref "U4") (pin "5") (pinfunction "2IN+_5") (pintype "input"))
    )
    (net (code "71") (name "Net-(P1-3)") (class "Default")
      (node (ref "P1") (pin "C") (pinfunction "3_C") (pintype "passive"))
      (node (ref "U1") (pin "2") (pinfunction "1IN-_2") (pintype "input"))
      (node (ref "U1") (pin "6") (pinfunction "2IN-_6") (pintype "input"))
      (node (ref "U2") (pin "2") (pinfunction "1IN-_2") (pintype "input"))
      (node (ref "U2") (pin "6") (pinfunction "2IN-_6") (pintype "input"))
      (node (ref "U3") (pin "2") (pinfunction "1IN-_2") (pintype "input"))
      (node (ref "U3") (pin "6") (pinfunction "2IN-_6") (pintype "input"))
      (node (ref "U4") (pin "2") (pinfunction "1IN-_2") (pintype "input"))
      (node (ref "U4") (pin "6") (pinfunction "2IN-_6") (pintype "input"))
    )
    (net (code "72") (name "Net-(R16-Pad2)") (class "Default")
      (node (ref "R16") (pin "2") (pinfunction "2_2") (pintype "passive"))
      (node (ref "U$1") (pin "P$2") (pinfunction "P$2_P$2") (pintype "bidirectional"))
    )
    (net (code "73") (name "Net-(R17-Pad2)") (class "Default")
      (node (ref "R17") (pin "2") (pinfunction "2_2") (pintype "passive"))
      (node (ref "U$1") (pin "P$3") (pinfunction "P$3_P$3") (pintype "bidirectional"))
    )
    (net (code "74") (name "Net-(T1-B)") (class "Default")
      (node (ref "R2") (pin "2") (pinfunction "2_2") (pintype "passive"))
      (node (ref "T1") (pin "1") (pinfunction "B_1") (pintype "passive"))
    )
    (net (code "75") (name "Net-(T1-C)") (class "Default")
      (node (ref "JP5") (pin "8") (pinfunction "8_8") (pintype "passive"))
      (node (ref "T1") (pin "3") (pinfunction "C_3") (pintype "passive"))
    )
    (net (code "76") (name "Net-(T2-B)") (class "Default")
      (node (ref "R3") (pin "2") (pinfunction "2_2") (pintype "passive"))
      (node (ref "T2") (pin "1") (pinfunction "B_1") (pintype "passive"))
    )
    (net (code "77") (name "Net-(T2-C)") (class "Default")
      (node (ref "JP5") (pin "7") (pinfunction "7_7") (pintype "passive"))
      (node (ref "T2") (pin "3") (pinfunction "C_3") (pintype "passive"))
    )
    (net (code "78") (name "Net-(T3-B)") (class "Default")
      (node (ref "R4") (pin "2") (pinfunction "2_2") (pintype "passive"))
      (node (ref "T3") (pin "1") (pinfunction "B_1") (pintype "passive"))
    )
    (net (code "79") (name "Net-(T3-C)") (class "Default")
      (node (ref "JP5") (pin "6") (pinfunction "6_6") (pintype "passive"))
      (node (ref "T3") (pin "3") (pinfunction "C_3") (pintype "passive"))
    )
    (net (code "80") (name "Net-(T4-B)") (class "Default")
      (node (ref "R5") (pin "2") (pinfunction "2_2") (pintype "passive"))
      (node (ref "T4") (pin "1") (pinfunction "B_1") (pintype "passive"))
    )
    (net (code "81") (name "Net-(T4-C)") (class "Default")
      (node (ref "JP5") (pin "5") (pinfunction "5_5") (pintype "passive"))
      (node (ref "T4") (pin "3") (pinfunction "C_3") (pintype "passive"))
    )
    (net (code "82") (name "Net-(T5-B)") (class "Default")
      (node (ref "R6") (pin "2") (pinfunction "2_2") (pintype "passive"))
      (node (ref "T5") (pin "1") (pinfunction "B_1") (pintype "passive"))
    )
    (net (code "83") (name "Net-(T5-C)") (class "Default")
      (node (ref "JP5") (pin "4") (pinfunction "4_4") (pintype "passive"))
      (node (ref "T5") (pin "3") (pinfunction "C_3") (pintype "passive"))
    )
    (net (code "84") (name "Net-(T6-B)") (class "Default")
      (node (ref "R7") (pin "2") (pinfunction "2_2") (pintype "passive"))
      (node (ref "T6") (pin "1") (pinfunction "B_1") (pintype "passive"))
    )
    (net (code "85") (name "Net-(T6-C)") (class "Default")
      (node (ref "JP5") (pin "3") (pinfunction "3_3") (pintype "passive"))
      (node (ref "T6") (pin "3") (pinfunction "C_3") (pintype "passive"))
    )
    (net (code "86") (name "Net-(T7-B)") (class "Default")
      (node (ref "R8") (pin "2") (pinfunction "2_2") (pintype "passive"))
      (node (ref "T7") (pin "1") (pinfunction "B_1") (pintype "passive"))
    )
    (net (code "87") (name "Net-(T7-C)") (class "Default")
      (node (ref "JP5") (pin "2") (pinfunction "2_2") (pintype "passive"))
      (node (ref "T7") (pin "3") (pinfunction "C_3") (pintype "passive"))
    )
    (net (code "88") (name "Net-(T8-B)") (class "Default")
      (node (ref "R9") (pin "2") (pinfunction "2_2") (pintype "passive"))
      (node (ref "T8") (pin "1") (pinfunction "B_1") (pintype "passive"))
    )
    (net (code "89") (name "Net-(T8-C)") (class "Default")
      (node (ref "JP5") (pin "1") (pinfunction "1_1") (pintype "passive"))
      (node (ref "T8") (pin "3") (pinfunction "C_3") (pintype "passive"))
    )
    (net (code "90") (name "VCC") (class "Default")
      (node (ref "+5") (pin "MP") (pinfunction "MP_MP") (pintype "passive"))
      (node (ref "C3") (pin "1") (pinfunction "1_1") (pintype "passive"))
      (node (ref "C4") (pin "1") (pinfunction "1_1") (pintype "passive"))
      (node (ref "C5") (pin "1") (pinfunction "1_1") (pintype "passive"))
      (node (ref "C6") (pin "1") (pinfunction "1_1") (pintype "passive"))
      (node (ref "IC1") (pin "17") (pinfunction "VCC1_17") (pintype "power_in"))
      (node (ref "IC1") (pin "27") (pinfunction "AVCC_27") (pintype "power_in"))
      (node (ref "IC1") (pin "38") (pinfunction "VCC2_38") (pintype "power_in"))
      (node (ref "IC1") (pin "5") (pinfunction "VCC_5") (pintype "power_in"))
      (node (ref "JP1") (pin "10") (pinfunction "10_10") (pintype "passive"))
      (node (ref "JP1") (pin "2") (pinfunction "2_2") (pintype "passive"))
      (node (ref "JP1") (pin "4") (pinfunction "4_4") (pintype "passive"))
      (node (ref "JP1") (pin "6") (pinfunction "6_6") (pintype "passive"))
      (node (ref "JP1") (pin "8") (pinfunction "8_8") (pintype "passive"))
      (node (ref "P1") (pin "A") (pinfunction "1_A") (pintype "passive"))
      (node (ref "R1") (pin "1") (pinfunction "1_1") (pintype "passive"))
      (node (ref "R15") (pin "1") (pinfunction "1_1") (pintype "passive"))
      (node (ref "R15") (pin "2") (pinfunction "2_2") (pintype "passive"))
      (node (ref "U1") (pin "8") (pinfunction "VDD_8") (pintype "power_in"))
      (node (ref "U2") (pin "8") (pinfunction "VDD_8") (pintype "power_in"))
      (node (ref "U3") (pin "8") (pinfunction "VDD_8") (pintype "power_in"))
      (node (ref "U4") (pin "8") (pinfunction "VDD_8") (pintype "power_in"))
    )
    (net (code "91") (name "unconnected-(IC1-AREF-Pad29)") (class "Default")
      (node (ref "IC1") (pin "29") (pinfunction "AREF_29") (pintype "passive"))
    )
    (net (code "92") (name "unconnected-(SW1-Pad3)") (class "Default")
      (node (ref "SW1") (pin "3") (pinfunction "3_3") (pintype "passive"))
    )
    (net (code "93") (name "unconnected-(SW1-Pad4)") (class "Default")
      (node (ref "SW1") (pin "4") (pinfunction "4_4") (pintype "passive"))
    )
  )
)
